# Atomic_Stick.net
KiCad netlist of a schematic drawn in EAGLE
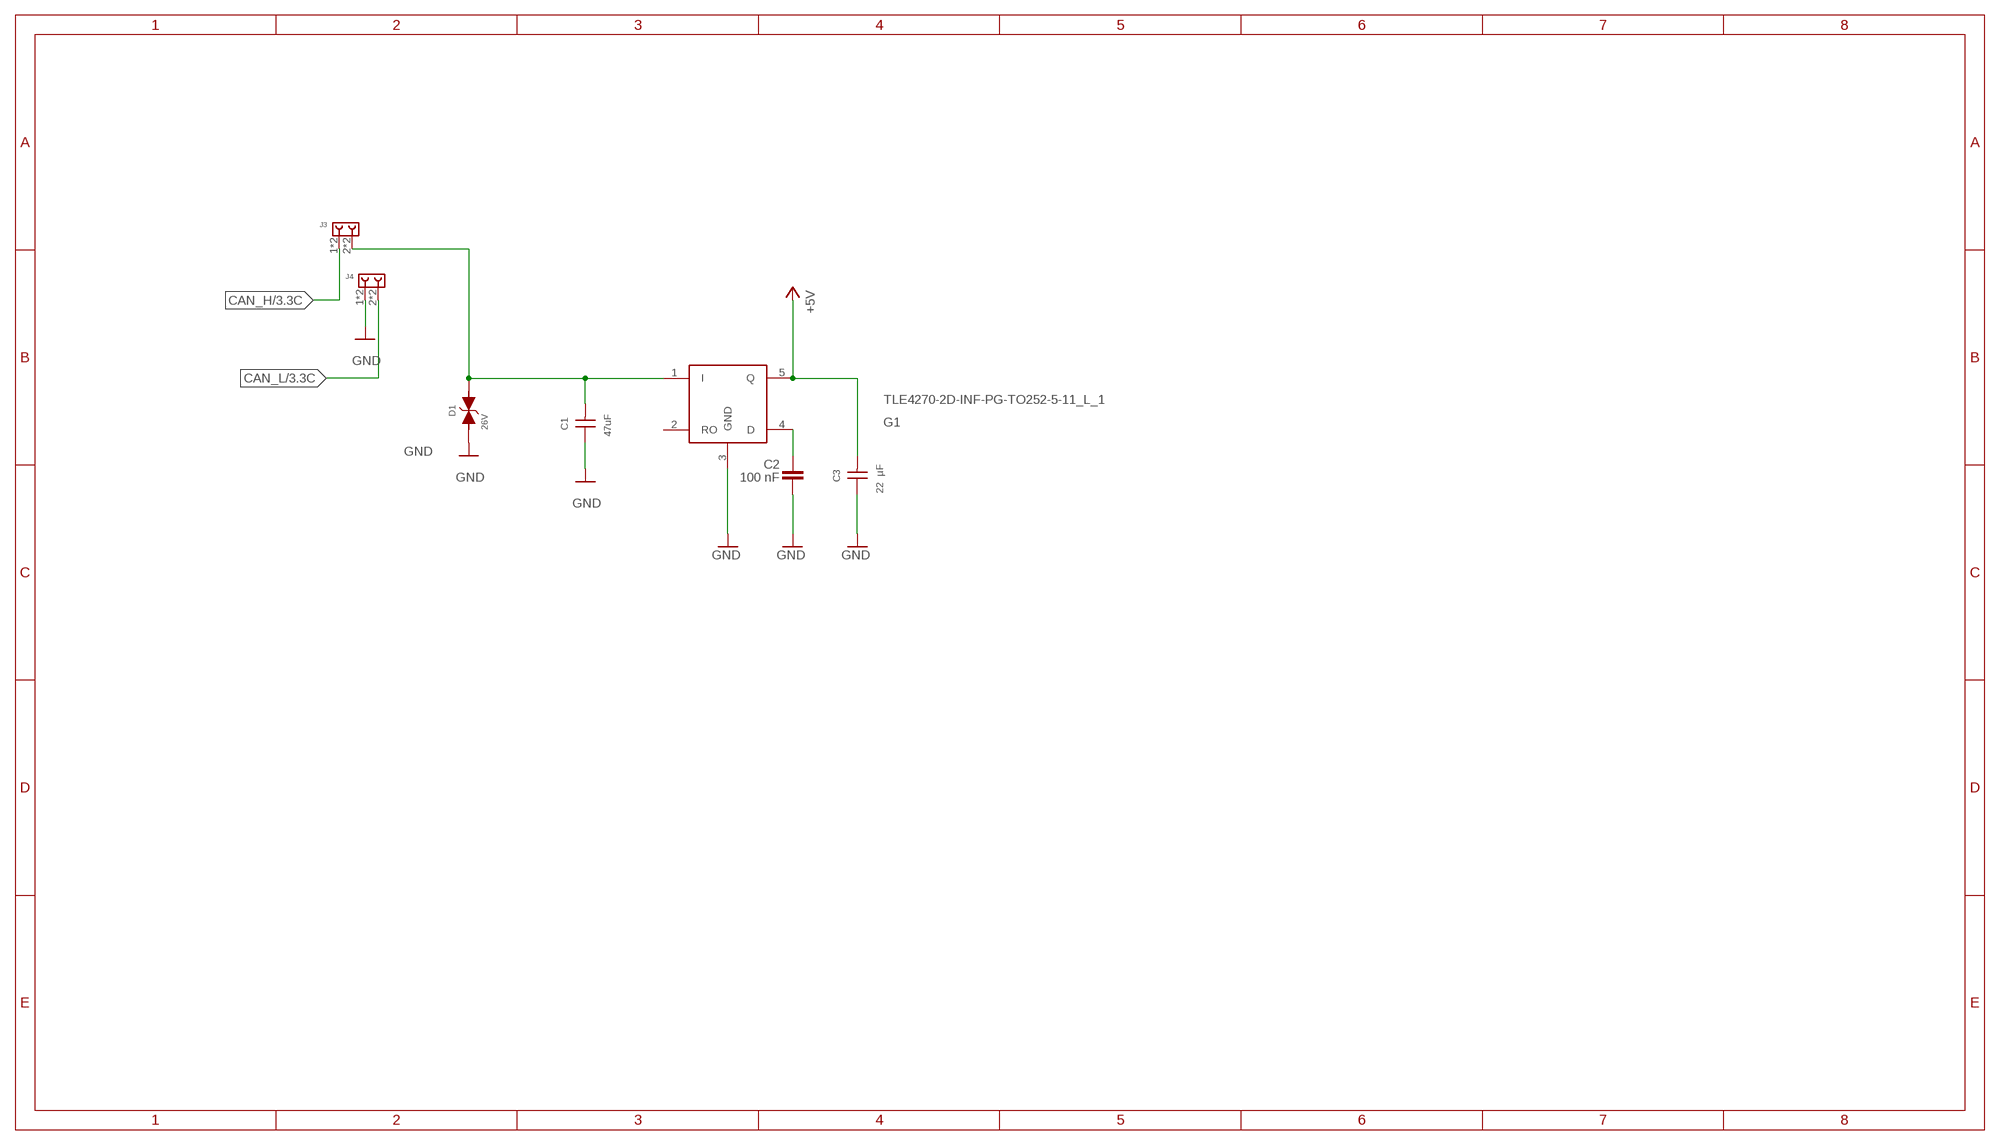
[diagram p0: schematic, sheet 1]
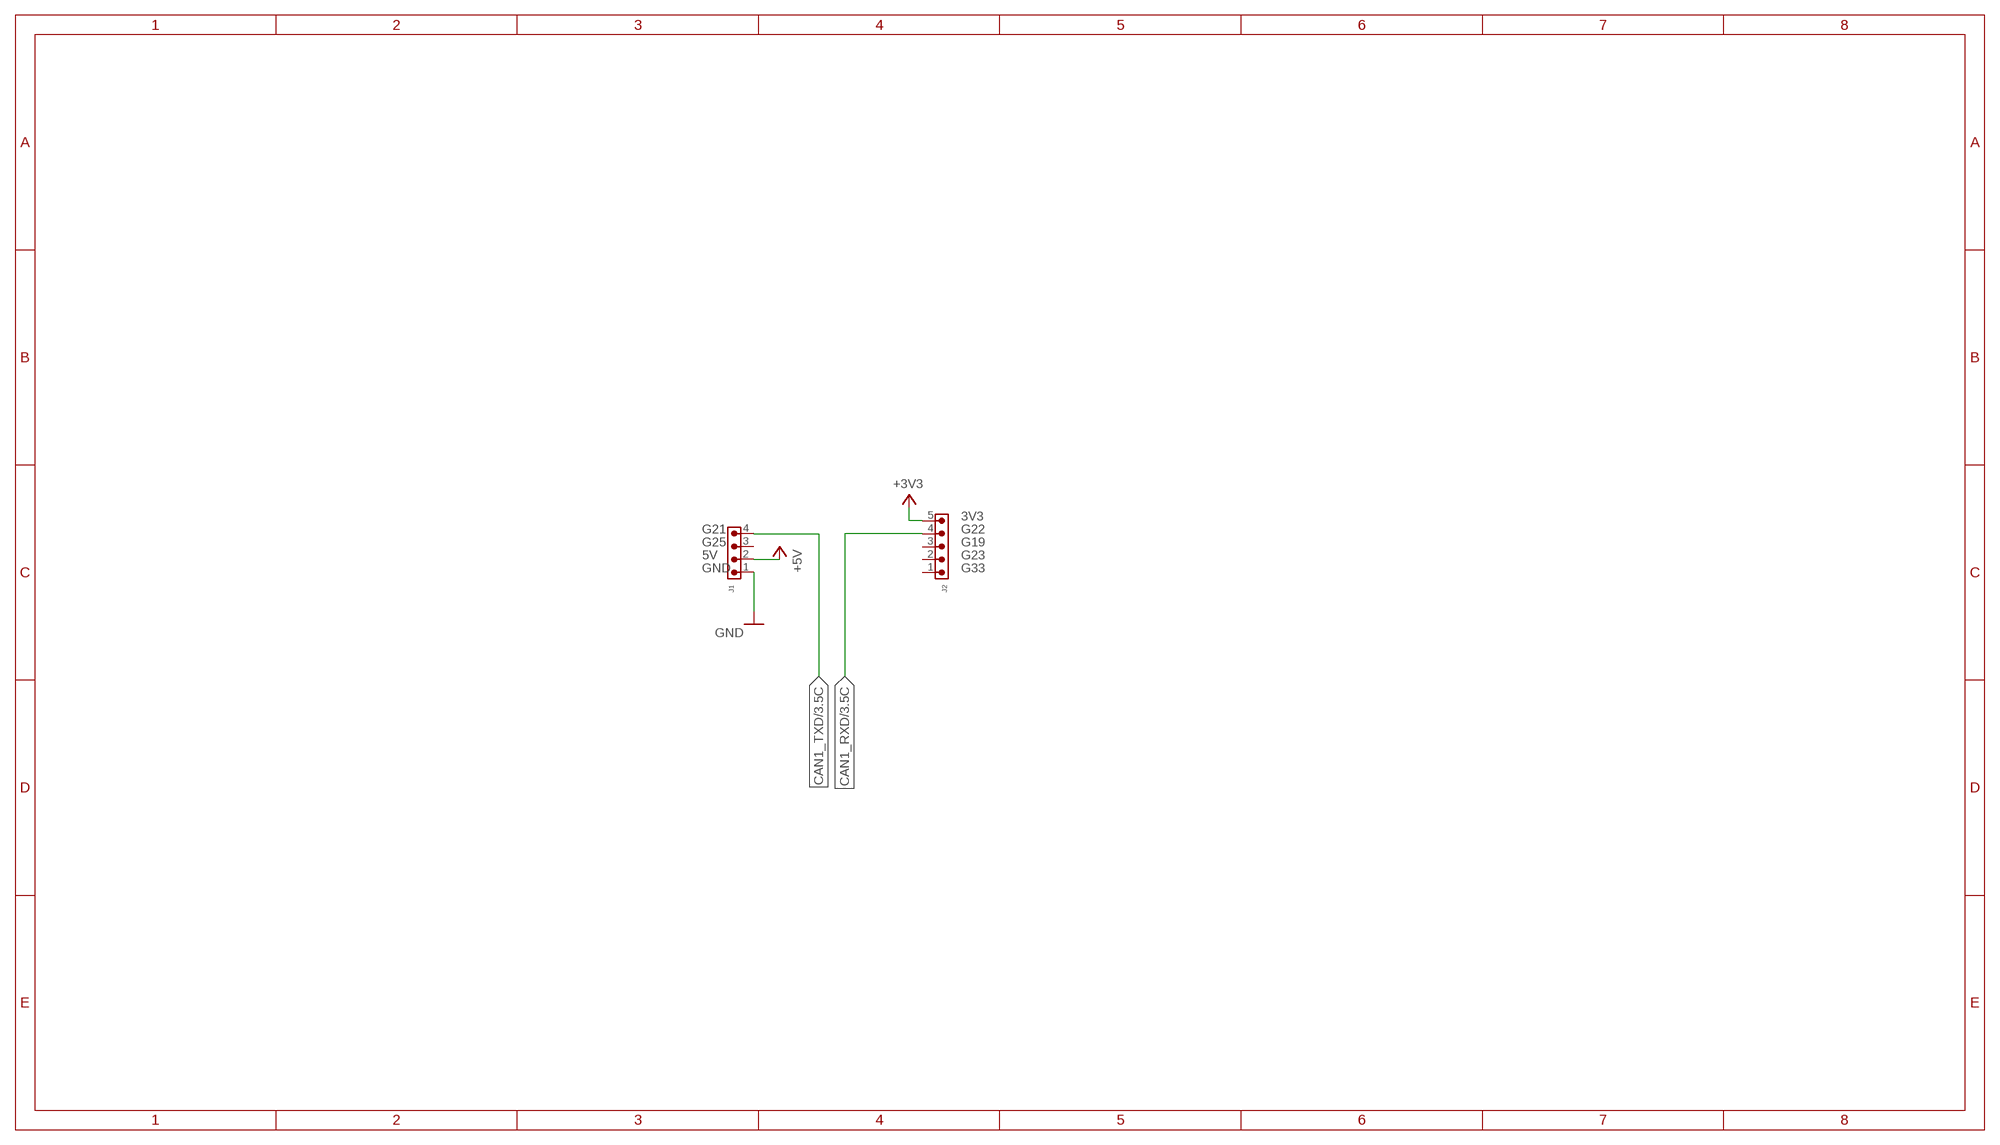
[diagram p1: schematic, sheet 2]
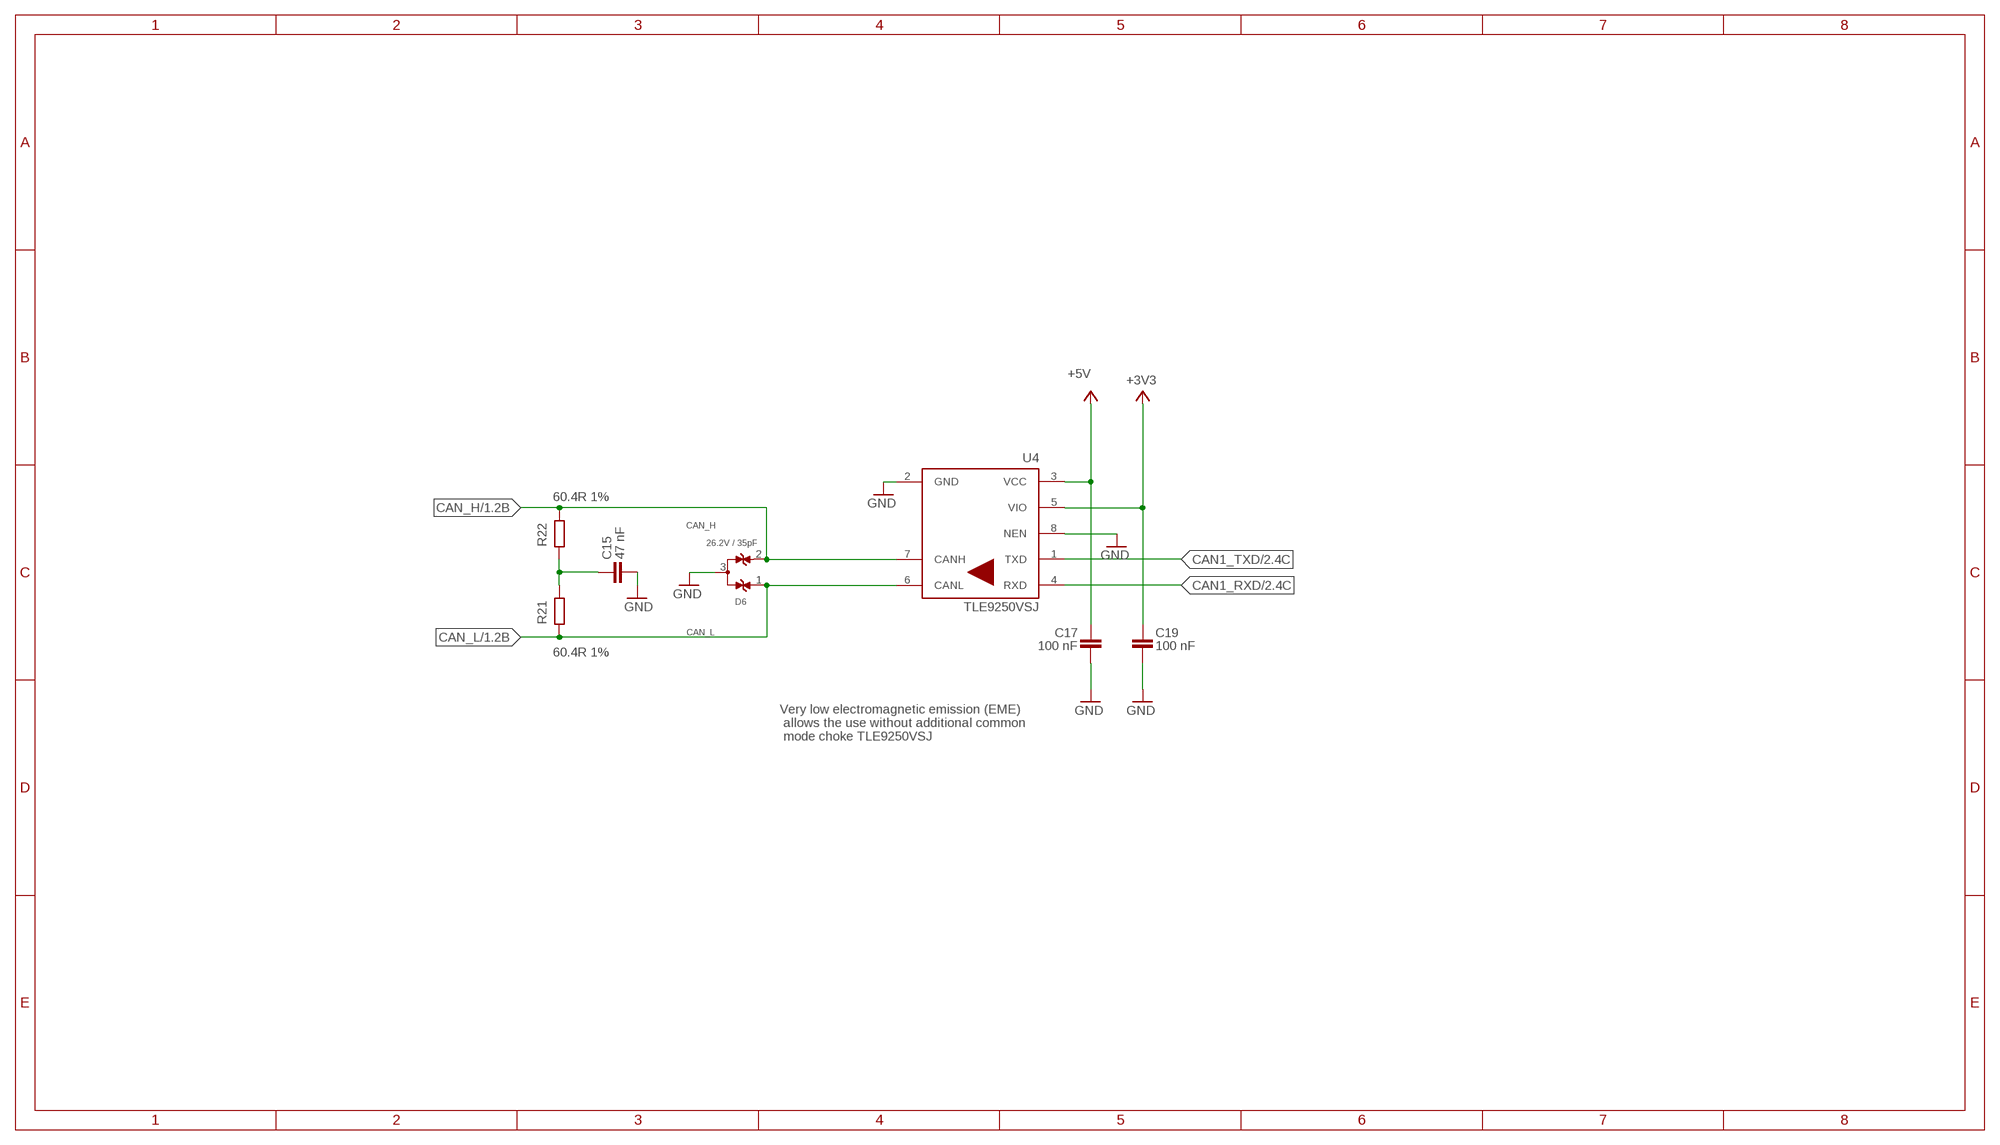
[diagram p2: schematic, sheet 3]

(export (version "E")
  (design (tool "Eeschema 10.0.6"))
  (components
    (comp (ref "J1")
      (value "6130XX11121_61300411121")
      (footprint "eagle-import:61300411121")
      (libsource (lib "eagle-import") (part "6130XX11121_61300411121"))
    )
    (comp (ref "J2")
      (value "6130XX11121_61300511121")
      (footprint "eagle-import:61300511121")
      (libsource (lib "eagle-import") (part "6130XX11121_61300511121"))
    )
    (comp (ref "C1")
      (value "47uF")
      (footprint "eagle-import:WCAP-CSGP_1210_H2.5")
      (libsource (lib "eagle-import") (part "WCAP-CSGP_1210_H2.5_25V(DC)_885012109014"))
    )
    (comp (ref "C2")
      (value "100 nF")
      (footprint "eagle-import:WCAP-CSGP_0402")
      (libsource (lib "eagle-import") (part "WCAP-CSGP_0402_16V(DC)_885012205037"))
    )
    (comp (ref "C3")
      (value "22 µF")
      (footprint "eagle-import:WCAP-CSGP_0805_H1.25_R")
      (libsource (lib "eagle-import") (part "WCAP-CSGP_0805_H1.25_10V(DC)_885012107011"))
    )
    (comp (ref "D1")
      (value "26V")
      (footprint "eagle-import:WE-TVSP_DO-214AC_BIDIRECTIONAL")
      (libsource (lib "eagle-import") (part "WE-TVSP_DO-214AC_400W_BI_824501261"))
    )
    (comp (ref "G1")
      (value "TLE4270-2D-INF-PG-TO252-5-11_L_1")
      (footprint "eagle-import:INF-PG-TO252-5-11_L_1PRIMARY")
      (libsource (lib "eagle-import") (part "TLE4270-2D-INF-PG-TO252-5-11_L_1"))
    )
    (comp (ref "J3")
      (value "695402400222")
      (footprint "eagle-import:695402400222")
      (libsource (lib "eagle-import") (part "695402400222"))
    )
    (comp (ref "J4")
      (value "695402400222")
      (footprint "eagle-import:695402400222")
      (libsource (lib "eagle-import") (part "695402400222"))
    )
    (comp (ref "C15")
      (value "47 nF")
      (footprint "eagle-import:WCAP-CSGP_0402")
      (libsource (lib "eagle-import") (part "WCAP-CSGP_0402_25V(DC)_885012205054"))
    )
    (comp (ref "C17")
      (value "100 nF")
      (footprint "eagle-import:WCAP-CSGP_0402")
      (libsource (lib "eagle-import") (part "WCAP-CSGP_0402_16V(DC)_885012205037"))
    )
    (comp (ref "C19")
      (value "100 nF")
      (footprint "eagle-import:WCAP-CSGP_0402")
      (libsource (lib "eagle-import") (part "WCAP-CSGP_0402_16V(DC)_885012205037"))
    )
    (comp (ref "D6")
      (value "26.2V / 35pF")
      (footprint "eagle-import:WE-TVS_SOT23-3L")
      (libsource (lib "eagle-import") (part "WE-TVS_SOT23-3L_824098024"))
    )
    (comp (ref "R21")
      (value "60.4R 1%")
      (footprint "eagle-import:WCAP-CSRF_0402")
      (fields (field (name "N") "SMD 0402 60.4ohms 1% AEC-Q200"))
      (libsource (lib "eagle-import") (part "R-0402_60.4OHMS_1%_AEC-Q200"))
    )
    (comp (ref "R22")
      (value "60.4R 1%")
      (footprint "eagle-import:WCAP-CSRF_0402")
      (fields (field (name "N") "SMD 0402 60.4ohms 1% AEC-Q200"))
      (libsource (lib "eagle-import") (part "R-0402_60.4OHMS_1%_AEC-Q200"))
    )
    (comp (ref "U4")
      (value "TLE9250VSJ")
      (footprint "eagle-import:SOIC127P602X173-8N-V")
      (libsource (lib "eagle-import") (part "TLE9250VSJ"))
    )
  )
  (nets
    (net (code "1") (name "+3V3") (class "Default")
      (node (ref "C19") (pin "1") (pinfunction "1_1") (pintype "passive"))
      (node (ref "J2") (pin "5") (pinfunction "5_5") (pintype "passive"))
      (node (ref "U4") (pin "5") (pinfunction "VIO_5") (pintype "input"))
    )
    (net (code "2") (name "+5V") (class "Default")
      (node (ref "C17") (pin "1") (pinfunction "1_1") (pintype "passive"))
      (node (ref "C3") (pin "2") (pinfunction "2_2") (pintype "passive"))
      (node (ref "G1") (pin "5") (pinfunction "Q_5") (pintype "power_in"))
      (node (ref "J1") (pin "2") (pinfunction "2_2") (pintype "passive"))
      (node (ref "U4") (pin "3") (pinfunction "VCC_3") (pintype "input"))
    )
    (net (code "3") (name "CAN1_RXD") (class "Default")
      (node (ref "J2") (pin "4") (pinfunction "4_4") (pintype "passive"))
      (node (ref "U4") (pin "4") (pinfunction "RXD_4") (pintype "output"))
    )
    (net (code "4") (name "CAN1_TXD") (class "Default")
      (node (ref "J1") (pin "4") (pinfunction "4_4") (pintype "passive"))
      (node (ref "U4") (pin "1") (pinfunction "TXD_1") (pintype "input"))
    )
    (net (code "5") (name "CAN_H") (class "Default")
      (node (ref "D6") (pin "2") (pinfunction "2_2") (pintype "passive"))
      (node (ref "J3") (pin "1") (pinfunction "1_1") (pintype "passive"))
      (node (ref "J3") (pin "A1") (pinfunction "1_A1") (pintype "passive"))
      (node (ref "R22") (pin "2") (pinfunction "2_2") (pintype "passive"))
      (node (ref "U4") (pin "7") (pinfunction "CANH_7") (pintype "bidirectional"))
    )
    (net (code "6") (name "CAN_L") (class "Default")
      (node (ref "D6") (pin "1") (pinfunction "1_1") (pintype "passive"))
      (node (ref "J4") (pin "2") (pinfunction "2_2") (pintype "passive"))
      (node (ref "J4") (pin "A2") (pinfunction "2_A2") (pintype "passive"))
      (node (ref "R21") (pin "1") (pinfunction "1_1") (pintype "passive"))
      (node (ref "U4") (pin "6") (pinfunction "CANL_6") (pintype "bidirectional"))
    )
    (net (code "7") (name "GND") (class "Default")
      (node (ref "C1") (pin "1") (pinfunction "1_1") (pintype "passive"))
      (node (ref "C15") (pin "2") (pinfunction "2_2") (pintype "passive"))
      (node (ref "C17") (pin "2") (pinfunction "2_2") (pintype "passive"))
      (node (ref "C19") (pin "2") (pinfunction "2_2") (pintype "passive"))
      (node (ref "C2") (pin "2") (pinfunction "2_2") (pintype "passive"))
      (node (ref "C3") (pin "1") (pinfunction "1_1") (pintype "passive"))
      (node (ref "D1") (pin "1") (pinfunction "1_1") (pintype "passive"))
      (node (ref "D6") (pin "3") (pinfunction "3_3") (pintype "passive"))
      (node (ref "G1") (pin "3") (pinfunction "GND_3") (pintype "power_in"))
      (node (ref "J1") (pin "1") (pinfunction "1_1") (pintype "passive"))
      (node (ref "J4") (pin "1") (pinfunction "1_1") (pintype "passive"))
      (node (ref "J4") (pin "A1") (pinfunction "1_A1") (pintype "passive"))
      (node (ref "U4") (pin "2") (pinfunction "GND_2") (pintype "power_in"))
      (node (ref "U4") (pin "8") (pinfunction "NEN_8") (pintype "input"))
    )
    (net (code "8") (name "Net-(C15-Pad1)") (class "Default")
      (node (ref "C15") (pin "1") (pinfunction "1_1") (pintype "passive"))
      (node (ref "R21") (pin "2") (pinfunction "2_2") (pintype "passive"))
      (node (ref "R22") (pin "1") (pinfunction "1_1") (pintype "passive"))
    )
    (net (code "9") (name "Net-(G1-D)") (class "Default")
      (node (ref "C2") (pin "1") (pinfunction "1_1") (pintype "passive"))
      (node (ref "G1") (pin "4") (pinfunction "D_4") (pintype "bidirectional"))
    )
    (net (code "10") (name "Net-(G1-I)") (class "Default")
      (node (ref "C1") (pin "2") (pinfunction "2_2") (pintype "passive"))
      (node (ref "D1") (pin "2") (pinfunction "2_2") (pintype "passive"))
      (node (ref "G1") (pin "1") (pinfunction "I_1") (pintype "power_in"))
      (node (ref "J3") (pin "2") (pinfunction "2_2") (pintype "passive"))
      (node (ref "J3") (pin "A2") (pinfunction "2_A2") (pintype "passive"))
    )
    (net (code "11") (name "unconnected-(G1-RO-Pad2)") (class "Default")
      (node (ref "G1") (pin "2") (pinfunction "RO_2") (pintype "output"))
    )
    (net (code "12") (name "unconnected-(J1-Pad3)") (class "Default")
      (node (ref "J1") (pin "3") (pinfunction "3_3") (pintype "passive"))
    )
    (net (code "13") (name "unconnected-(J2-Pad1)") (class "Default")
      (node (ref "J2") (pin "1") (pinfunction "1_1") (pintype "passive"))
    )
    (net (code "14") (name "unconnected-(J2-Pad2)") (class "Default")
      (node (ref "J2") (pin "2") (pinfunction "2_2") (pintype "passive"))
    )
    (net (code "15") (name "unconnected-(J2-Pad3)") (class "Default")
      (node (ref "J2") (pin "3") (pinfunction "3_3") (pintype "passive"))
    )
  )
)
